# COM_R_SEPT28.net
KiCad netlist of a schematic drawn in EAGLE
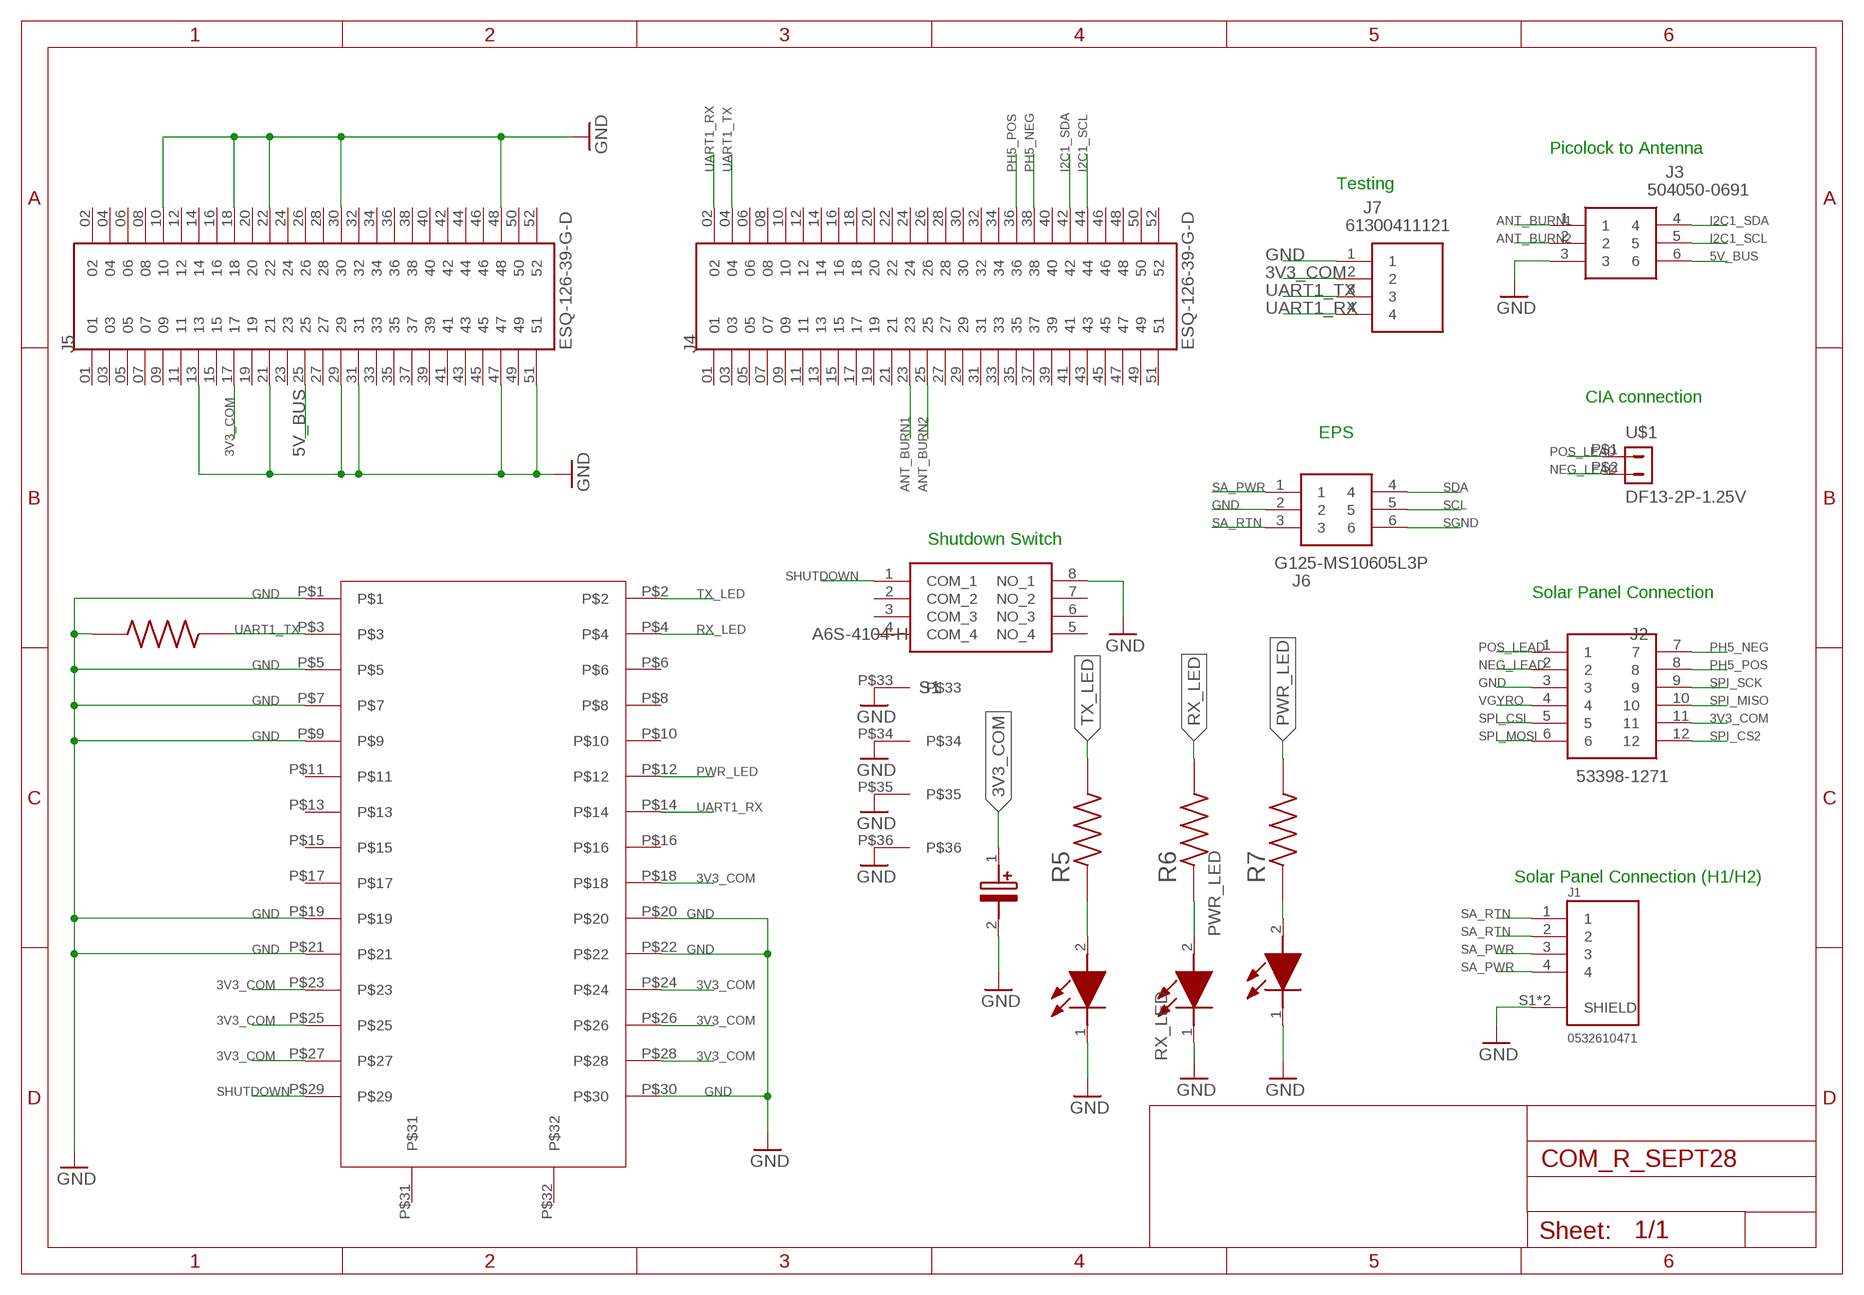
[diagram p0: schematic, sheet 1]

(export (version "E")
  (design (tool "Eeschema 10.0.6"))
  (components
    (comp (ref "C2")
      (value "293D106X0010A2TE3")
      (footprint "eagle-import:CAPPM3216X180N")
      (fields (field (name "MOUSER_PART_NUMBER") "74-293D106X0010A2TE3"))
      (libsource (lib "eagle-import") (part "293D106X0010A2TE3"))
    )
    (comp (ref "J1")
      (value "0532610471")
      (footprint "eagle-import:MOLEX_0532610471")
      (fields (field (name "MF") "Molex"))
      (libsource (lib "eagle-import") (part "0532610471"))
    )
    (comp (ref "J2")
      (value "53398-1271")
      (footprint "eagle-import:53398-1271")
      (fields (field (name "MOUSER_PART_NUMBER") "538-53398-1271"))
      (libsource (lib "eagle-import") (part "53398-1271"))
    )
    (comp (ref "J3")
      (value "504050-0691")
      (footprint "eagle-import:504050-0691_2")
      (fields (field (name "MOUSER_PART_NUMBER") "538-504050-0691"))
      (libsource (lib "eagle-import") (part "504050-0691"))
    )
    (comp (ref "J4")
      (value "ESQ-126-39-G-D")
      (footprint "eagle-import:SAMTEC_ESQ-126-39-G-D")
      (fields (field (name "MF") "Samtec"))
      (libsource (lib "eagle-import") (part "ESQ-126-39-G-D"))
    )
    (comp (ref "J5")
      (value "ESQ-126-39-G-D")
      (footprint "eagle-import:SAMTEC_ESQ-126-39-G-D")
      (fields (field (name "MF") "Samtec"))
      (libsource (lib "eagle-import") (part "ESQ-126-39-G-D"))
    )
    (comp (ref "J6")
      (value "G125-MS10605L3P")
      (footprint "eagle-import:G125-MS10605L3P")
      (fields (field (name "MOUSER_PART_NUMBER") "855-G125-MS10605L3P"))
      (libsource (lib "eagle-import") (part "G125-MS10605L3P"))
    )
    (comp (ref "J7")
      (value "61300411121")
      (footprint "eagle-import:HDRV4W95P0X254_1X4_1016X254X85")
      (fields (field (name "MOUSER_PART_NUMBER") "710-61300411121"))
      (libsource (lib "eagle-import") (part "61300411121"))
    )
    (comp (ref "PWR_LED")
      (value "HSMQ-C170-T0000")
      (footprint "eagle-import:LEDC2012X90N")
      (fields (field (name "MOUSER_PART_NUMBER") "630-HSMQ-C170-T0000"))
      (libsource (lib "eagle-import") (part "HSMQ-C170-T0000"))
    )
    (comp (ref "R3")
      (value "TNPW080510K0BETY")
      (footprint "eagle-import:RESC2012X55N")
      (fields (field (name "DIGI-KEY_PART_NUMBER") "541-3913-1-ND") (field (name "MF") "Vishay"))
      (libsource (lib "eagle-import") (part "TNPW080510K0BETY"))
    )
    (comp (ref "R5")
      (value "Y40621K00000Q0R")
      (footprint "eagle-import:RESC2012X64N")
      (fields (field (name "DIGI-KEY_PART_NUMBER") "Y4062-1.0KACT-ND") (field (name "MF") "Vishay"))
      (libsource (lib "eagle-import") (part "Y40621K00000Q0R"))
    )
    (comp (ref "R6")
      (value "Y40621K00000Q0R")
      (footprint "eagle-import:RESC2012X64N")
      (fields (field (name "DIGI-KEY_PART_NUMBER") "Y4062-1.0KACT-ND") (field (name "MF") "Vishay"))
      (libsource (lib "eagle-import") (part "Y40621K00000Q0R"))
    )
    (comp (ref "R7")
      (value "Y40621K00000Q0R")
      (footprint "eagle-import:RESC2012X64N")
      (fields (field (name "DIGI-KEY_PART_NUMBER") "Y4062-1.0KACT-ND") (field (name "MF") "Vishay"))
      (libsource (lib "eagle-import") (part "Y40621K00000Q0R"))
    )
    (comp (ref "RX_LED")
      (value "HSMQ-C170-T0000")
      (footprint "eagle-import:LEDC2012X90N")
      (fields (field (name "MOUSER_PART_NUMBER") "630-HSMQ-C170-T0000"))
      (libsource (lib "eagle-import") (part "HSMQ-C170-T0000"))
    )
    (comp (ref "S1")
      (value "A6S-4104-H")
      (footprint "eagle-import:A6S4104H")
      (fields (field (name "MOUSER_PART_NUMBER") "653-A6S-4104-H"))
      (libsource (lib "eagle-import") (part "A6S-4104-H"))
    )
    (comp (ref "TX_LED")
      (value "HSMQ-C170-T0000")
      (footprint "eagle-import:LEDC2012X90N")
      (fields (field (name "MOUSER_PART_NUMBER") "630-HSMQ-C170-T0000"))
      (libsource (lib "eagle-import") (part "HSMQ-C170-T0000"))
    )
    (comp (ref "U$1")
      (value "DF13-2P-1.25V")
      (footprint "eagle-import:DF13C-2P-1.25V")
      (libsource (lib "eagle-import") (part "DF13-2P-1.25V"))
    )
    (comp (ref "U$3")
      (value "KYOCERA_5046_30PIN")
      (footprint "eagle-import:KYOCERA_5046_30PIN")
      (libsource (lib "eagle-import") (part "KYOCERA_5046_30PIN"))
    )
  )
  (nets
    (net (code "1") (name "/5V_BUS") (class "Default")
      (node (ref "J3") (pin "6") (pinfunction "6_6") (pintype "bidirectional"))
      (node (ref "J5") (pin "25") (pinfunction "25_25") (pintype "passive"))
    )
    (net (code "2") (name "/ANT_BURN1") (class "Default")
      (node (ref "J3") (pin "1") (pinfunction "1_1") (pintype "bidirectional"))
      (node (ref "J4") (pin "23") (pinfunction "23_23") (pintype "passive"))
    )
    (net (code "3") (name "/ANT_BURN2") (class "Default")
      (node (ref "J3") (pin "2") (pinfunction "2_2") (pintype "bidirectional"))
      (node (ref "J4") (pin "25") (pinfunction "25_25") (pintype "passive"))
    )
    (net (code "4") (name "/I2C1_SCL") (class "Default")
      (node (ref "J3") (pin "5") (pinfunction "5_5") (pintype "bidirectional"))
      (node (ref "J4") (pin "44") (pinfunction "44_44") (pintype "passive"))
    )
    (net (code "5") (name "/I2C1_SDA") (class "Default")
      (node (ref "J3") (pin "4") (pinfunction "4_4") (pintype "bidirectional"))
      (node (ref "J4") (pin "42") (pinfunction "42_42") (pintype "passive"))
    )
    (net (code "6") (name "/NEG_LEAD") (class "Default")
      (node (ref "J2") (pin "2") (pinfunction "2_2") (pintype "bidirectional"))
      (node (ref "U$1") (pin "P$2") (pinfunction "2_P$2") (pintype "passive"))
    )
    (net (code "7") (name "/PH5_NEG") (class "Default")
      (node (ref "J2") (pin "7") (pinfunction "7_7") (pintype "bidirectional"))
      (node (ref "J4") (pin "38") (pinfunction "38_38") (pintype "passive"))
    )
    (net (code "8") (name "/PH5_POS") (class "Default")
      (node (ref "J2") (pin "8") (pinfunction "8_8") (pintype "bidirectional"))
      (node (ref "J4") (pin "36") (pinfunction "36_36") (pintype "passive"))
    )
    (net (code "9") (name "/POS_LEAD") (class "Default")
      (node (ref "J2") (pin "1") (pinfunction "1_1") (pintype "bidirectional"))
      (node (ref "U$1") (pin "P$1") (pinfunction "1_P$1") (pintype "passive"))
    )
    (net (code "10") (name "/SA_PWR") (class "Default")
      (node (ref "J1") (pin "3") (pinfunction "3_3") (pintype "passive"))
      (node (ref "J1") (pin "4") (pinfunction "4_4") (pintype "passive"))
      (node (ref "J6") (pin "1") (pinfunction "1_1") (pintype "bidirectional"))
    )
    (net (code "11") (name "/SA_RTN") (class "Default")
      (node (ref "J1") (pin "1") (pinfunction "1_1") (pintype "passive"))
      (node (ref "J1") (pin "2") (pinfunction "2_2") (pintype "passive"))
      (node (ref "J6") (pin "3") (pinfunction "3_3") (pintype "bidirectional"))
    )
    (net (code "12") (name "/SCL") (class "Default")
      (node (ref "J6") (pin "5") (pinfunction "5_5") (pintype "bidirectional"))
    )
    (net (code "13") (name "/SDA") (class "Default")
      (node (ref "J6") (pin "4") (pinfunction "4_4") (pintype "bidirectional"))
    )
    (net (code "14") (name "/SGND") (class "Default")
      (node (ref "J6") (pin "6") (pinfunction "6_6") (pintype "bidirectional"))
    )
    (net (code "15") (name "/SHUTDOWN") (class "Default")
      (node (ref "S1") (pin "1") (pinfunction "COM_1_1") (pintype "bidirectional"))
      (node (ref "U$3") (pin "P$29") (pinfunction "P$29_P$29") (pintype "bidirectional"))
    )
    (net (code "16") (name "/SPI_CS2") (class "Default")
      (node (ref "J2") (pin "12") (pinfunction "12_12") (pintype "bidirectional"))
    )
    (net (code "17") (name "/SPI_CSI") (class "Default")
      (node (ref "J2") (pin "5") (pinfunction "5_5") (pintype "bidirectional"))
    )
    (net (code "18") (name "/SPI_MISO") (class "Default")
      (node (ref "J2") (pin "10") (pinfunction "10_10") (pintype "bidirectional"))
    )
    (net (code "19") (name "/SPI_MOSI") (class "Default")
      (node (ref "J2") (pin "6") (pinfunction "6_6") (pintype "bidirectional"))
    )
    (net (code "20") (name "/SPI_SCK") (class "Default")
      (node (ref "J2") (pin "9") (pinfunction "9_9") (pintype "bidirectional"))
    )
    (net (code "21") (name "/UART1_RX") (class "Default")
      (node (ref "J4") (pin "02") (pinfunction "02_02") (pintype "passive"))
      (node (ref "J7") (pin "4") (pinfunction "4_4") (pintype "bidirectional"))
      (node (ref "U$3") (pin "P$14") (pinfunction "P$14_P$14") (pintype "bidirectional"))
    )
    (net (code "22") (name "/UART1_TX") (class "Default")
      (node (ref "J4") (pin "04") (pinfunction "04_04") (pintype "passive"))
      (node (ref "J7") (pin "3") (pinfunction "3_3") (pintype "bidirectional"))
      (node (ref "R3") (pin "2") (pinfunction "2_2") (pintype "passive"))
      (node (ref "U$3") (pin "P$3") (pinfunction "P$3_P$3") (pintype "bidirectional"))
    )
    (net (code "23") (name "/VGYRO") (class "Default")
      (node (ref "J2") (pin "4") (pinfunction "4_4") (pintype "bidirectional"))
    )
    (net (code "24") (name "3V3_COM") (class "Default")
      (node (ref "C2") (pin "1") (pinfunction "+_1") (pintype "bidirectional"))
      (node (ref "J2") (pin "11") (pinfunction "11_11") (pintype "bidirectional"))
      (node (ref "J5") (pin "17") (pinfunction "17_17") (pintype "passive"))
      (node (ref "J7") (pin "2") (pinfunction "2_2") (pintype "bidirectional"))
      (node (ref "U$3") (pin "P$18") (pinfunction "P$18_P$18") (pintype "bidirectional"))
      (node (ref "U$3") (pin "P$23") (pinfunction "P$23_P$23") (pintype "bidirectional"))
      (node (ref "U$3") (pin "P$24") (pinfunction "P$24_P$24") (pintype "bidirectional"))
      (node (ref "U$3") (pin "P$25") (pinfunction "P$25_P$25") (pintype "bidirectional"))
      (node (ref "U$3") (pin "P$26") (pinfunction "P$26_P$26") (pintype "bidirectional"))
      (node (ref "U$3") (pin "P$27") (pinfunction "P$27_P$27") (pintype "bidirectional"))
      (node (ref "U$3") (pin "P$28") (pinfunction "P$28_P$28") (pintype "bidirectional"))
    )
    (net (code "25") (name "GND") (class "Default")
      (node (ref "C2") (pin "2") (pinfunction "-_2") (pintype "bidirectional"))
      (node (ref "J1") (pin "S1") (pinfunction "SHIELD_S1") (pintype "passive"))
      (node (ref "J1") (pin "S2") (pinfunction "SHIELD_S2") (pintype "passive"))
      (node (ref "J2") (pin "3") (pinfunction "3_3") (pintype "bidirectional"))
      (node (ref "J3") (pin "3") (pinfunction "3_3") (pintype "bidirectional"))
      (node (ref "J5") (pin "10") (pinfunction "10_10") (pintype "passive"))
      (node (ref "J5") (pin "13") (pinfunction "13_13") (pintype "passive"))
      (node (ref "J5") (pin "18") (pinfunction "18_18") (pintype "passive"))
      (node (ref "J5") (pin "21") (pinfunction "21_21") (pintype "passive"))
      (node (ref "J5") (pin "22") (pinfunction "22_22") (pintype "passive"))
      (node (ref "J5") (pin "29") (pinfunction "29_29") (pintype "passive"))
      (node (ref "J5") (pin "30") (pinfunction "30_30") (pintype "passive"))
      (node (ref "J5") (pin "31") (pinfunction "31_31") (pintype "passive"))
      (node (ref "J5") (pin "47") (pinfunction "47_47") (pintype "passive"))
      (node (ref "J5") (pin "48") (pinfunction "48_48") (pintype "passive"))
      (node (ref "J5") (pin "51") (pinfunction "51_51") (pintype "passive"))
      (node (ref "J6") (pin "2") (pinfunction "2_2") (pintype "bidirectional"))
      (node (ref "J7") (pin "1") (pinfunction "1_1") (pintype "bidirectional"))
      (node (ref "PWR_LED") (pin "1") (pinfunction "K_1") (pintype "bidirectional"))
      (node (ref "R3") (pin "1") (pinfunction "1_1") (pintype "passive"))
      (node (ref "RX_LED") (pin "1") (pinfunction "K_1") (pintype "bidirectional"))
      (node (ref "S1") (pin "8") (pinfunction "NO_1_8") (pintype "bidirectional"))
      (node (ref "TX_LED") (pin "1") (pinfunction "K_1") (pintype "bidirectional"))
      (node (ref "U$3") (pin "P$1") (pinfunction "P$1_P$1") (pintype "bidirectional"))
      (node (ref "U$3") (pin "P$19") (pinfunction "P$19_P$19") (pintype "bidirectional"))
      (node (ref "U$3") (pin "P$20") (pinfunction "P$20_P$20") (pintype "bidirectional"))
      (node (ref "U$3") (pin "P$21") (pinfunction "P$21_P$21") (pintype "bidirectional"))
      (node (ref "U$3") (pin "P$22") (pinfunction "P$22_P$22") (pintype "bidirectional"))
      (node (ref "U$3") (pin "P$30") (pinfunction "P$30_P$30") (pintype "bidirectional"))
      (node (ref "U$3") (pin "P$33") (pinfunction "P$33_P$33") (pintype "bidirectional"))
      (node (ref "U$3") (pin "P$34") (pinfunction "P$34_P$34") (pintype "bidirectional"))
      (node (ref "U$3") (pin "P$35") (pinfunction "P$35_P$35") (pintype "bidirectional"))
      (node (ref "U$3") (pin "P$36") (pinfunction "P$36_P$36") (pintype "bidirectional"))
      (node (ref "U$3") (pin "P$5") (pinfunction "P$5_P$5") (pintype "bidirectional"))
      (node (ref "U$3") (pin "P$7") (pinfunction "P$7_P$7") (pintype "bidirectional"))
      (node (ref "U$3") (pin "P$9") (pinfunction "P$9_P$9") (pintype "bidirectional"))
    )
    (net (code "26") (name "Net-(PWR_LED-A)") (class "Default")
      (node (ref "PWR_LED") (pin "2") (pinfunction "A_2") (pintype "bidirectional"))
      (node (ref "R7") (pin "1") (pinfunction "1_1") (pintype "passive"))
    )
    (net (code "27") (name "Net-(RX_LED-A)") (class "Default")
      (node (ref "R6") (pin "1") (pinfunction "1_1") (pintype "passive"))
      (node (ref "RX_LED") (pin "2") (pinfunction "A_2") (pintype "bidirectional"))
    )
    (net (code "28") (name "Net-(TX_LED-A)") (class "Default")
      (node (ref "R5") (pin "1") (pinfunction "1_1") (pintype "passive"))
      (node (ref "TX_LED") (pin "2") (pinfunction "A_2") (pintype "bidirectional"))
    )
    (net (code "29") (name "PWR_LED") (class "Default")
      (node (ref "R7") (pin "2") (pinfunction "2_2") (pintype "passive"))
      (node (ref "U$3") (pin "P$12") (pinfunction "P$12_P$12") (pintype "bidirectional"))
    )
    (net (code "30") (name "RX_LED") (class "Default")
      (node (ref "R6") (pin "2") (pinfunction "2_2") (pintype "passive"))
      (node (ref "U$3") (pin "P$4") (pinfunction "P$4_P$4") (pintype "bidirectional"))
    )
    (net (code "31") (name "TX_LED") (class "Default")
      (node (ref "R5") (pin "2") (pinfunction "2_2") (pintype "passive"))
      (node (ref "U$3") (pin "P$2") (pinfunction "P$2_P$2") (pintype "bidirectional"))
    )
    (net (code "32") (name "unconnected-(J4-Pad01)") (class "Default")
      (node (ref "J4") (pin "01") (pinfunction "01_01") (pintype "passive"))
    )
    (net (code "33") (name "unconnected-(J4-Pad03)") (class "Default")
      (node (ref "J4") (pin "03") (pinfunction "03_03") (pintype "passive"))
    )
    (net (code "34") (name "unconnected-(J4-Pad05)") (class "Default")
      (node (ref "J4") (pin "05") (pinfunction "05_05") (pintype "passive"))
    )
    (net (code "35") (name "unconnected-(J4-Pad06)") (class "Default")
      (node (ref "J4") (pin "06") (pinfunction "06_06") (pintype "passive"))
    )
    (net (code "36") (name "unconnected-(J4-Pad07)") (class "Default")
      (node (ref "J4") (pin "07") (pinfunction "07_07") (pintype "passive"))
    )
    (net (code "37") (name "unconnected-(J4-Pad08)") (class "Default")
      (node (ref "J4") (pin "08") (pinfunction "08_08") (pintype "passive"))
    )
    (net (code "38") (name "unconnected-(J4-Pad09)") (class "Default")
      (node (ref "J4") (pin "09") (pinfunction "09_09") (pintype "passive"))
    )
    (net (code "39") (name "unconnected-(J4-Pad10)") (class "Default")
      (node (ref "J4") (pin "10") (pinfunction "10_10") (pintype "passive"))
    )
    (net (code "40") (name "unconnected-(J4-Pad11)") (class "Default")
      (node (ref "J4") (pin "11") (pinfunction "11_11") (pintype "passive"))
    )
    (net (code "41") (name "unconnected-(J4-Pad12)") (class "Default")
      (node (ref "J4") (pin "12") (pinfunction "12_12") (pintype "passive"))
    )
    (net (code "42") (name "unconnected-(J4-Pad13)") (class "Default")
      (node (ref "J4") (pin "13") (pinfunction "13_13") (pintype "passive"))
    )
    (net (code "43") (name "unconnected-(J4-Pad14)") (class "Default")
      (node (ref "J4") (pin "14") (pinfunction "14_14") (pintype "passive"))
    )
    (net (code "44") (name "unconnected-(J4-Pad15)") (class "Default")
      (node (ref "J4") (pin "15") (pinfunction "15_15") (pintype "passive"))
    )
    (net (code "45") (name "unconnected-(J4-Pad16)") (class "Default")
      (node (ref "J4") (pin "16") (pinfunction "16_16") (pintype "passive"))
    )
    (net (code "46") (name "unconnected-(J4-Pad17)") (class "Default")
      (node (ref "J4") (pin "17") (pinfunction "17_17") (pintype "passive"))
    )
    (net (code "47") (name "unconnected-(J4-Pad18)") (class "Default")
      (node (ref "J4") (pin "18") (pinfunction "18_18") (pintype "passive"))
    )
    (net (code "48") (name "unconnected-(J4-Pad19)") (class "Default")
      (node (ref "J4") (pin "19") (pinfunction "19_19") (pintype "passive"))
    )
    (net (code "49") (name "unconnected-(J4-Pad20)") (class "Default")
      (node (ref "J4") (pin "20") (pinfunction "20_20") (pintype "passive"))
    )
    (net (code "50") (name "unconnected-(J4-Pad21)") (class "Default")
      (node (ref "J4") (pin "21") (pinfunction "21_21") (pintype "passive"))
    )
    (net (code "51") (name "unconnected-(J4-Pad22)") (class "Default")
      (node (ref "J4") (pin "22") (pinfunction "22_22") (pintype "passive"))
    )
    (net (code "52") (name "unconnected-(J4-Pad24)") (class "Default")
      (node (ref "J4") (pin "24") (pinfunction "24_24") (pintype "passive"))
    )
    (net (code "53") (name "unconnected-(J4-Pad26)") (class "Default")
      (node (ref "J4") (pin "26") (pinfunction "26_26") (pintype "passive"))
    )
    (net (code "54") (name "unconnected-(J4-Pad27)") (class "Default")
      (node (ref "J4") (pin "27") (pinfunction "27_27") (pintype "passive"))
    )
    (net (code "55") (name "unconnected-(J4-Pad28)") (class "Default")
      (node (ref "J4") (pin "28") (pinfunction "28_28") (pintype "passive"))
    )
    (net (code "56") (name "unconnected-(J4-Pad29)") (class "Default")
      (node (ref "J4") (pin "29") (pinfunction "29_29") (pintype "passive"))
    )
    (net (code "57") (name "unconnected-(J4-Pad30)") (class "Default")
      (node (ref "J4") (pin "30") (pinfunction "30_30") (pintype "passive"))
    )
    (net (code "58") (name "unconnected-(J4-Pad31)") (class "Default")
      (node (ref "J4") (pin "31") (pinfunction "31_31") (pintype "passive"))
    )
    (net (code "59") (name "unconnected-(J4-Pad32)") (class "Default")
      (node (ref "J4") (pin "32") (pinfunction "32_32") (pintype "passive"))
    )
    (net (code "60") (name "unconnected-(J4-Pad33)") (class "Default")
      (node (ref "J4") (pin "33") (pinfunction "33_33") (pintype "passive"))
    )
    (net (code "61") (name "unconnected-(J4-Pad34)") (class "Default")
      (node (ref "J4") (pin "34") (pinfunction "34_34") (pintype "passive"))
    )
    (net (code "62") (name "unconnected-(J4-Pad35)") (class "Default")
      (node (ref "J4") (pin "35") (pinfunction "35_35") (pintype "passive"))
    )
    (net (code "63") (name "unconnected-(J4-Pad37)") (class "Default")
      (node (ref "J4") (pin "37") (pinfunction "37_37") (pintype "passive"))
    )
    (net (code "64") (name "unconnected-(J4-Pad39)") (class "Default")
      (node (ref "J4") (pin "39") (pinfunction "39_39") (pintype "passive"))
    )
    (net (code "65") (name "unconnected-(J4-Pad40)") (class "Default")
      (node (ref "J4") (pin "40") (pinfunction "40_40") (pintype "passive"))
    )
    (net (code "66") (name "unconnected-(J4-Pad41)") (class "Default")
      (node (ref "J4") (pin "41") (pinfunction "41_41") (pintype "passive"))
    )
    (net (code "67") (name "unconnected-(J4-Pad43)") (class "Default")
      (node (ref "J4") (pin "43") (pinfunction "43_43") (pintype "passive"))
    )
    (net (code "68") (name "unconnected-(J4-Pad45)") (class "Default")
      (node (ref "J4") (pin "45") (pinfunction "45_45") (pintype "passive"))
    )
    (net (code "69") (name "unconnected-(J4-Pad46)") (class "Default")
      (node (ref "J4") (pin "46") (pinfunction "46_46") (pintype "passive"))
    )
    (net (code "70") (name "unconnected-(J4-Pad47)") (class "Default")
      (node (ref "J4") (pin "47") (pinfunction "47_47") (pintype "passive"))
    )
    (net (code "71") (name "unconnected-(J4-Pad48)") (class "Default")
      (node (ref "J4") (pin "48") (pinfunction "48_48") (pintype "passive"))
    )
    (net (code "72") (name "unconnected-(J4-Pad49)") (class "Default")
      (node (ref "J4") (pin "49") (pinfunction "49_49") (pintype "passive"))
    )
    (net (code "73") (name "unconnected-(J4-Pad50)") (class "Default")
      (node (ref "J4") (pin "50") (pinfunction "50_50") (pintype "passive"))
    )
    (net (code "74") (name "unconnected-(J4-Pad51)") (class "Default")
      (node (ref "J4") (pin "51") (pinfunction "51_51") (pintype "passive"))
    )
    (net (code "75") (name "unconnected-(J4-Pad52)") (class "Default")
      (node (ref "J4") (pin "52") (pinfunction "52_52") (pintype "passive"))
    )
    (net (code "76") (name "unconnected-(J5-Pad01)") (class "Default")
      (node (ref "J5") (pin "01") (pinfunction "01_01") (pintype "passive"))
    )
    (net (code "77") (name "unconnected-(J5-Pad02)") (class "Default")
      (node (ref "J5") (pin "02") (pinfunction "02_02") (pintype "passive"))
    )
    (net (code "78") (name "unconnected-(J5-Pad03)") (class "Default")
      (node (ref "J5") (pin "03") (pinfunction "03_03") (pintype "passive"))
    )
    (net (code "79") (name "unconnected-(J5-Pad04)") (class "Default")
      (node (ref "J5") (pin "04") (pinfunction "04_04") (pintype "passive"))
    )
    (net (code "80") (name "unconnected-(J5-Pad05)") (class "Default")
      (node (ref "J5") (pin "05") (pinfunction "05_05") (pintype "passive"))
    )
    (net (code "81") (name "unconnected-(J5-Pad06)") (class "Default")
      (node (ref "J5") (pin "06") (pinfunction "06_06") (pintype "passive"))
    )
    (net (code "82") (name "unconnected-(J5-Pad07)") (class "Default")
      (node (ref "J5") (pin "07") (pinfunction "07_07") (pintype "passive"))
    )
    (net (code "83") (name "unconnected-(J5-Pad08)") (class "Default")
      (node (ref "J5") (pin "08") (pinfunction "08_08") (pintype "passive"))
    )
    (net (code "84") (name "unconnected-(J5-Pad09)") (class "Default")
      (node (ref "J5") (pin "09") (pinfunction "09_09") (pintype "passive"))
    )
    (net (code "85") (name "unconnected-(J5-Pad11)") (class "Default")
      (node (ref "J5") (pin "11") (pinfunction "11_11") (pintype "passive"))
    )
    (net (code "86") (name "unconnected-(J5-Pad12)") (class "Default")
      (node (ref "J5") (pin "12") (pinfunction "12_12") (pintype "passive"))
    )
    (net (code "87") (name "unconnected-(J5-Pad14)") (class "Default")
      (node (ref "J5") (pin "14") (pinfunction "14_14") (pintype "passive"))
    )
    (net (code "88") (name "unconnected-(J5-Pad15)") (class "Default")
      (node (ref "J5") (pin "15") (pinfunction "15_15") (pintype "passive"))
    )
    (net (code "89") (name "unconnected-(J5-Pad16)") (class "Default")
      (node (ref "J5") (pin "16") (pinfunction "16_16") (pintype "passive"))
    )
    (net (code "90") (name "unconnected-(J5-Pad19)") (class "Default")
      (node (ref "J5") (pin "19") (pinfunction "19_19") (pintype "passive"))
    )
    (net (code "91") (name "unconnected-(J5-Pad20)") (class "Default")
      (node (ref "J5") (pin "20") (pinfunction "20_20") (pintype "passive"))
    )
    (net (code "92") (name "unconnected-(J5-Pad23)") (class "Default")
      (node (ref "J5") (pin "23") (pinfunction "23_23") (pintype "passive"))
    )
    (net (code "93") (name "unconnected-(J5-Pad24)") (class "Default")
      (node (ref "J5") (pin "24") (pinfunction "24_24") (pintype "passive"))
    )
    (net (code "94") (name "unconnected-(J5-Pad26)") (class "Default")
      (node (ref "J5") (pin "26") (pinfunction "26_26") (pintype "passive"))
    )
    (net (code "95") (name "unconnected-(J5-Pad27)") (class "Default")
      (node (ref "J5") (pin "27") (pinfunction "27_27") (pintype "passive"))
    )
    (net (code "96") (name "unconnected-(J5-Pad28)") (class "Default")
      (node (ref "J5") (pin "28") (pinfunction "28_28") (pintype "passive"))
    )
    (net (code "97") (name "unconnected-(J5-Pad32)") (class "Default")
      (node (ref "J5") (pin "32") (pinfunction "32_32") (pintype "passive"))
    )
    (net (code "98") (name "unconnected-(J5-Pad33)") (class "Default")
      (node (ref "J5") (pin "33") (pinfunction "33_33") (pintype "passive"))
    )
    (net (code "99") (name "unconnected-(J5-Pad34)") (class "Default")
      (node (ref "J5") (pin "34") (pinfunction "34_34") (pintype "passive"))
    )
    (net (code "100") (name "unconnected-(J5-Pad35)") (class "Default")
      (node (ref "J5") (pin "35") (pinfunction "35_35") (pintype "passive"))
    )
    (net (code "101") (name "unconnected-(J5-Pad36)") (class "Default")
      (node (ref "J5") (pin "36") (pinfunction "36_36") (pintype "passive"))
    )
    (net (code "102") (name "unconnected-(J5-Pad37)") (class "Default")
      (node (ref "J5") (pin "37") (pinfunction "37_37") (pintype "passive"))
    )
    (net (code "103") (name "unconnected-(J5-Pad38)") (class "Default")
      (node (ref "J5") (pin "38") (pinfunction "38_38") (pintype "passive"))
    )
    (net (code "104") (name "unconnected-(J5-Pad39)") (class "Default")
      (node (ref "J5") (pin "39") (pinfunction "39_39") (pintype "passive"))
    )
    (net (code "105") (name "unconnected-(J5-Pad40)") (class "Default")
      (node (ref "J5") (pin "40") (pinfunction "40_40") (pintype "passive"))
    )
    (net (code "106") (name "unconnected-(J5-Pad41)") (class "Default")
      (node (ref "J5") (pin "41") (pinfunction "41_41") (pintype "passive"))
    )
    (net (code "107") (name "unconnected-(J5-Pad42)") (class "Default")
      (node (ref "J5") (pin "42") (pinfunction "42_42") (pintype "passive"))
    )
    (net (code "108") (name "unconnected-(J5-Pad43)") (class "Default")
      (node (ref "J5") (pin "43") (pinfunction "43_43") (pintype "passive"))
    )
    (net (code "109") (name "unconnected-(J5-Pad44)") (class "Default")
      (node (ref "J5") (pin "44") (pinfunction "44_44") (pintype "passive"))
    )
    (net (code "110") (name "unconnected-(J5-Pad45)") (class "Default")
      (node (ref "J5") (pin "45") (pinfunction "45_45") (pintype "passive"))
    )
    (net (code "111") (name "unconnected-(J5-Pad46)") (class "Default")
      (node (ref "J5") (pin "46") (pinfunction "46_46") (pintype "passive"))
    )
    (net (code "112") (name "unconnected-(J5-Pad49)") (class "Default")
      (node (ref "J5") (pin "49") (pinfunction "49_49") (pintype "passive"))
    )
    (net (code "113") (name "unconnected-(J5-Pad50)") (class "Default")
      (node (ref "J5") (pin "50") (pinfunction "50_50") (pintype "passive"))
    )
    (net (code "114") (name "unconnected-(J5-Pad52)") (class "Default")
      (node (ref "J5") (pin "52") (pinfunction "52_52") (pintype "passive"))
    )
    (net (code "115") (name "unconnected-(S1-COM_2-Pad2)") (class "Default")
      (node (ref "S1") (pin "2") (pinfunction "COM_2_2") (pintype "bidirectional"))
    )
    (net (code "116") (name "unconnected-(S1-COM_3-Pad3)") (class "Default")
      (node (ref "S1") (pin "3") (pinfunction "COM_3_3") (pintype "bidirectional"))
    )
    (net (code "117") (name "unconnected-(S1-COM_4-Pad4)") (class "Default")
      (node (ref "S1") (pin "4") (pinfunction "COM_4_4") (pintype "bidirectional"))
    )
    (net (code "118") (name "unconnected-(S1-NO_2-Pad7)") (class "Default")
      (node (ref "S1") (pin "7") (pinfunction "NO_2_7") (pintype "bidirectional"))
    )
    (net (code "119") (name "unconnected-(S1-NO_3-Pad6)") (class "Default")
      (node (ref "S1") (pin "6") (pinfunction "NO_3_6") (pintype "bidirectional"))
    )
    (net (code "120") (name "unconnected-(S1-NO_4-Pad5)") (class "Default")
      (node (ref "S1") (pin "5") (pinfunction "NO_4_5") (pintype "bidirectional"))
    )
    (net (code "121") (name "unconnected-(U$3-PadP$6)") (class "Default")
      (node (ref "U$3") (pin "P$6") (pinfunction "P$6_P$6") (pintype "bidirectional"))
    )
    (net (code "122") (name "unconnected-(U$3-PadP$8)") (class "Default")
      (node (ref "U$3") (pin "P$8") (pinfunction "P$8_P$8") (pintype "bidirectional"))
    )
    (net (code "123") (name "unconnected-(U$3-PadP$10)") (class "Default")
      (node (ref "U$3") (pin "P$10") (pinfunction "P$10_P$10") (pintype "bidirectional"))
    )
    (net (code "124") (name "unconnected-(U$3-PadP$11)") (class "Default")
      (node (ref "U$3") (pin "P$11") (pinfunction "P$11_P$11") (pintype "bidirectional"))
    )
    (net (code "125") (name "unconnected-(U$3-PadP$13)") (class "Default")
      (node (ref "U$3") (pin "P$13") (pinfunction "P$13_P$13") (pintype "bidirectional"))
    )
    (net (code "126") (name "unconnected-(U$3-PadP$15)") (class "Default")
      (node (ref "U$3") (pin "P$15") (pinfunction "P$15_P$15") (pintype "bidirectional"))
    )
    (net (code "127") (name "unconnected-(U$3-PadP$16)") (class "Default")
      (node (ref "U$3") (pin "P$16") (pinfunction "P$16_P$16") (pintype "bidirectional"))
    )
    (net (code "128") (name "unconnected-(U$3-PadP$17)") (class "Default")
      (node (ref "U$3") (pin "P$17") (pinfunction "P$17_P$17") (pintype "bidirectional"))
    )
    (net (code "129") (name "unconnected-(U$3-PadP$31)") (class "Default")
      (node (ref "U$3") (pin "P$31") (pinfunction "P$31_P$31") (pintype "bidirectional"))
    )
    (net (code "130") (name "unconnected-(U$3-PadP$32)") (class "Default")
      (node (ref "U$3") (pin "P$32") (pinfunction "P$32_P$32") (pintype "bidirectional"))
    )
  )
)
